# board_power_supply_lm26480.net
KiCad netlist of a schematic drawn in EAGLE
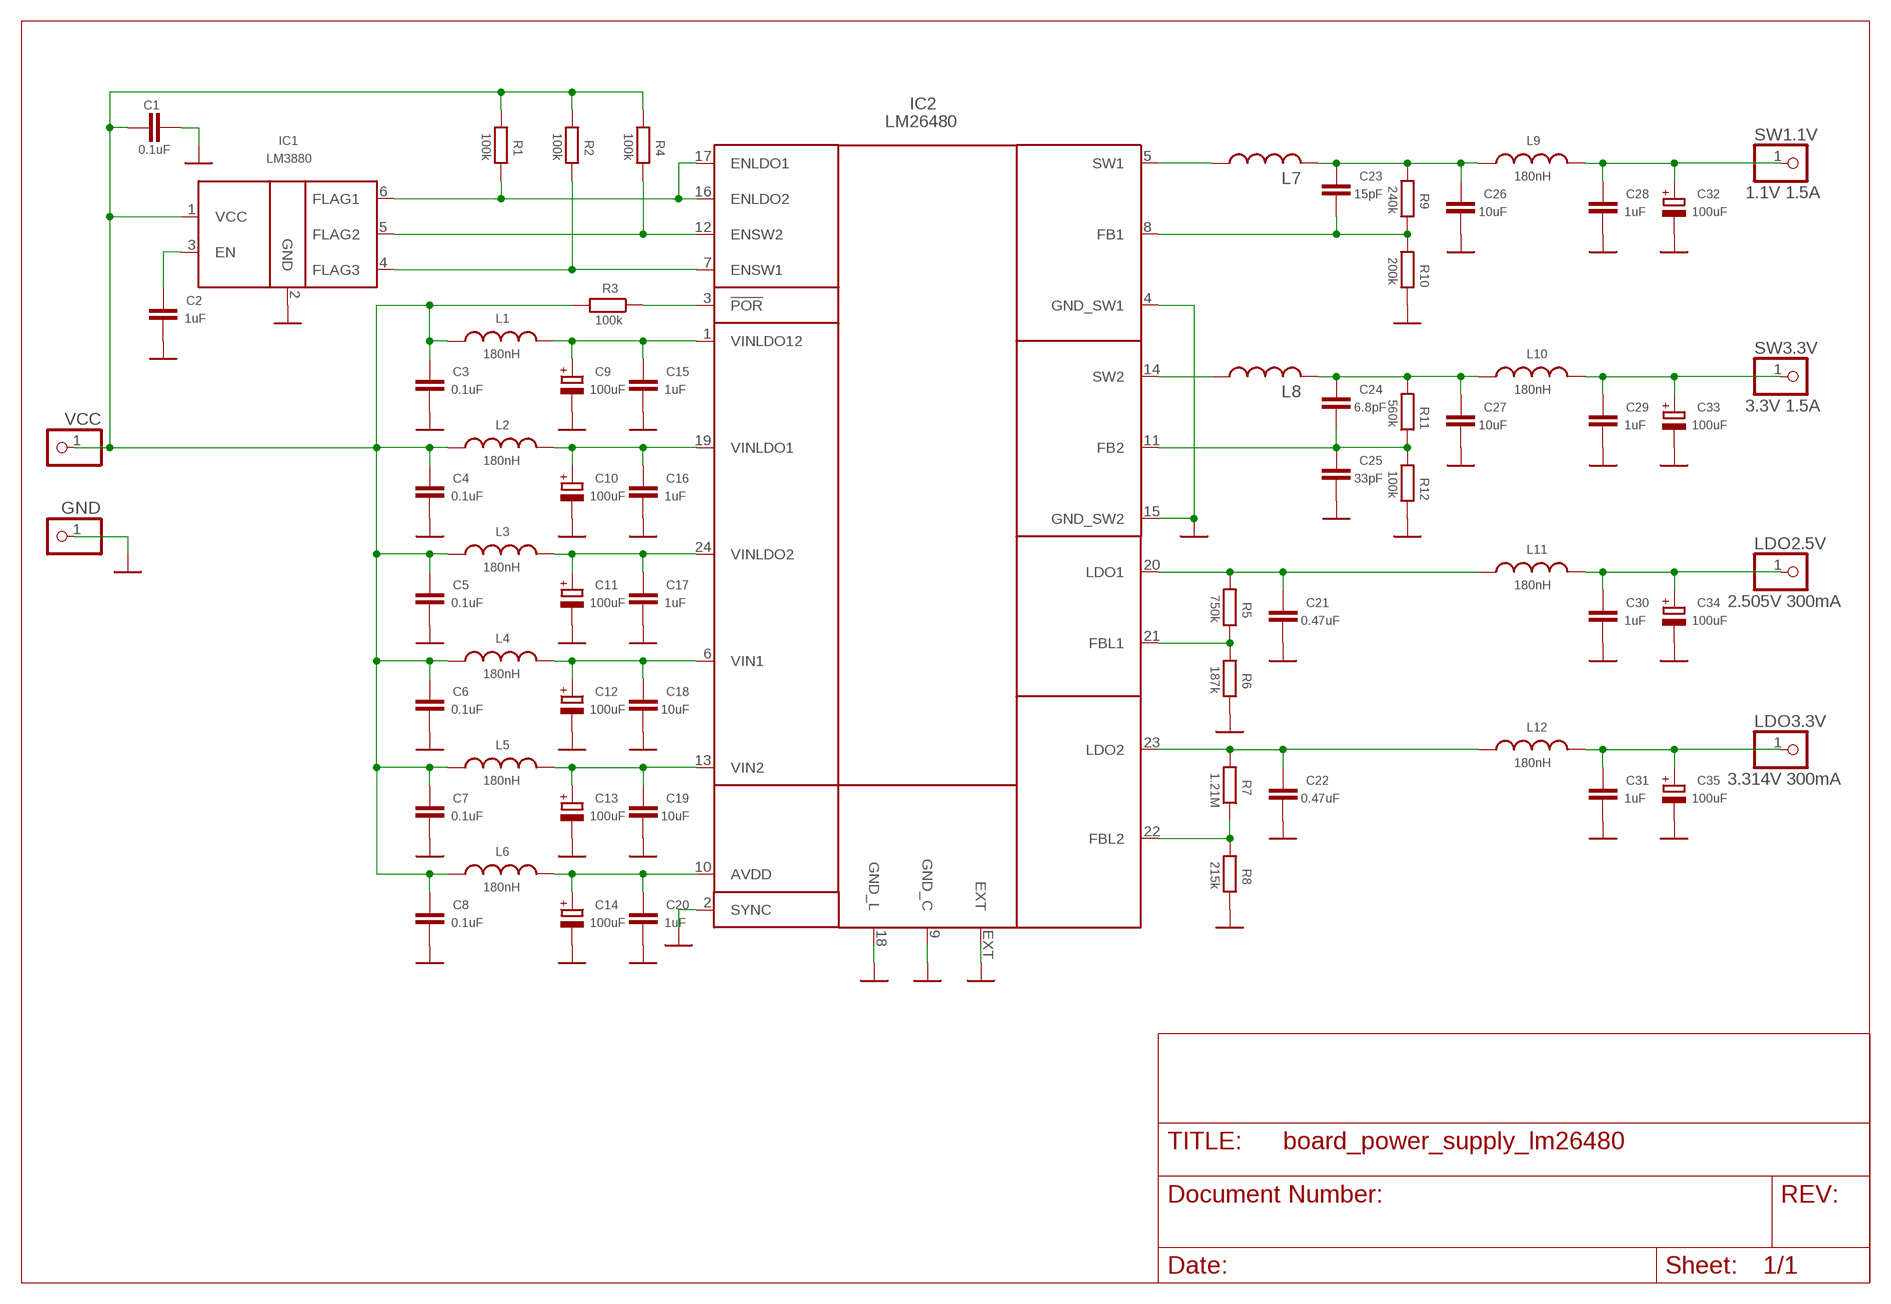
[diagram p0: schematic, sheet 1]

(export (version "E")
  (design (tool "Eeschema 10.0.6"))
  (components
    (comp (ref "C1")
      (value "0.1uF")
      (footprint "eagle-import:SMD0603")
      (libsource (lib "eagle-import") (part "C0603"))
    )
    (comp (ref "C2")
      (value "1uF")
      (footprint "eagle-import:SMD0603")
      (libsource (lib "eagle-import") (part "C0603"))
    )
    (comp (ref "C3")
      (value "0.1uF")
      (footprint "eagle-import:SMD0603")
      (libsource (lib "eagle-import") (part "C0603"))
    )
    (comp (ref "C4")
      (value "0.1uF")
      (footprint "eagle-import:SMD0603")
      (libsource (lib "eagle-import") (part "C0603"))
    )
    (comp (ref "C5")
      (value "0.1uF")
      (footprint "eagle-import:SMD0603")
      (libsource (lib "eagle-import") (part "C0603"))
    )
    (comp (ref "C6")
      (value "0.1uF")
      (footprint "eagle-import:SMD0603")
      (libsource (lib "eagle-import") (part "C0603"))
    )
    (comp (ref "C7")
      (value "0.1uF")
      (footprint "eagle-import:SMD0603")
      (libsource (lib "eagle-import") (part "C0603"))
    )
    (comp (ref "C8")
      (value "0.1uF")
      (footprint "eagle-import:SMD0603")
      (libsource (lib "eagle-import") (part "C0603"))
    )
    (comp (ref "C9")
      (value "100uF")
      (footprint "eagle-import:SMC_B")
      (libsource (lib "eagle-import") (part "CPOLSMC_B"))
    )
    (comp (ref "C10")
      (value "100uF")
      (footprint "eagle-import:SMC_B")
      (libsource (lib "eagle-import") (part "CPOLSMC_B"))
    )
    (comp (ref "C11")
      (value "100uF")
      (footprint "eagle-import:SMC_B")
      (libsource (lib "eagle-import") (part "CPOLSMC_B"))
    )
    (comp (ref "C12")
      (value "100uF")
      (footprint "eagle-import:SMC_B")
      (libsource (lib "eagle-import") (part "CPOLSMC_B"))
    )
    (comp (ref "C13")
      (value "100uF")
      (footprint "eagle-import:SMC_B")
      (libsource (lib "eagle-import") (part "CPOLSMC_B"))
    )
    (comp (ref "C14")
      (value "100uF")
      (footprint "eagle-import:SMC_B")
      (libsource (lib "eagle-import") (part "CPOLSMC_B"))
    )
    (comp (ref "C15")
      (value "1uF")
      (footprint "eagle-import:SMD0402")
      (libsource (lib "eagle-import") (part "C0402"))
    )
    (comp (ref "C16")
      (value "1uF")
      (footprint "eagle-import:SMD0402")
      (libsource (lib "eagle-import") (part "C0402"))
    )
    (comp (ref "C17")
      (value "1uF")
      (footprint "eagle-import:SMD0402")
      (libsource (lib "eagle-import") (part "C0402"))
    )
    (comp (ref "C18")
      (value "10uF")
      (footprint "eagle-import:SMD0805")
      (libsource (lib "eagle-import") (part "C0805"))
    )
    (comp (ref "C19")
      (value "10uF")
      (footprint "eagle-import:SMD0805")
      (libsource (lib "eagle-import") (part "C0805"))
    )
    (comp (ref "C20")
      (value "1uF")
      (footprint "eagle-import:SMD0402")
      (libsource (lib "eagle-import") (part "C0402"))
    )
    (comp (ref "C21")
      (value "0.47uF")
      (footprint "eagle-import:SMD0603")
      (libsource (lib "eagle-import") (part "C0603"))
    )
    (comp (ref "C22")
      (value "0.47uF")
      (footprint "eagle-import:SMD0603")
      (libsource (lib "eagle-import") (part "C0603"))
    )
    (comp (ref "C23")
      (value "15pF")
      (footprint "eagle-import:SMD0603")
      (libsource (lib "eagle-import") (part "C0603"))
    )
    (comp (ref "C24")
      (value "6.8pF")
      (footprint "eagle-import:SMD0603")
      (libsource (lib "eagle-import") (part "C0603"))
    )
    (comp (ref "C25")
      (value "33pF")
      (footprint "eagle-import:SMD0603")
      (libsource (lib "eagle-import") (part "C0603"))
    )
    (comp (ref "C26")
      (value "10uF")
      (footprint "eagle-import:SMD0805")
      (libsource (lib "eagle-import") (part "C0805"))
    )
    (comp (ref "C27")
      (value "10uF")
      (footprint "eagle-import:SMD0805")
      (libsource (lib "eagle-import") (part "C0805"))
    )
    (comp (ref "C28")
      (value "1uF")
      (footprint "eagle-import:SMD0603")
      (libsource (lib "eagle-import") (part "C0603"))
    )
    (comp (ref "C29")
      (value "1uF")
      (footprint "eagle-import:SMD0603")
      (libsource (lib "eagle-import") (part "C0603"))
    )
    (comp (ref "C30")
      (value "1uF")
      (footprint "eagle-import:SMD0603")
      (libsource (lib "eagle-import") (part "C0603"))
    )
    (comp (ref "C31")
      (value "1uF")
      (footprint "eagle-import:SMD0603")
      (libsource (lib "eagle-import") (part "C0603"))
    )
    (comp (ref "C32")
      (value "100uF")
      (footprint "eagle-import:SMC_B")
      (libsource (lib "eagle-import") (part "CPOLSMC_B"))
    )
    (comp (ref "C33")
      (value "100uF")
      (footprint "eagle-import:SMC_B")
      (libsource (lib "eagle-import") (part "CPOLSMC_B"))
    )
    (comp (ref "C34")
      (value "100uF")
      (footprint "eagle-import:SMC_B")
      (libsource (lib "eagle-import") (part "CPOLSMC_B"))
    )
    (comp (ref "C35")
      (value "100uF")
      (footprint "eagle-import:SMC_B")
      (libsource (lib "eagle-import") (part "CPOLSMC_B"))
    )
    (comp (ref "GND")
      (value "PINHD-1X1")
      (footprint "eagle-import:1X01")
      (libsource (lib "eagle-import") (part "PINHD-1X1"))
    )
    (comp (ref "IC1")
      (value "LM3880")
      (footprint "eagle-import:SOT23-6")
      (libsource (lib "eagle-import") (part "LM3880"))
    )
    (comp (ref "IC2")
      (value "LM26480")
      (footprint "eagle-import:WQFN24")
      (libsource (lib "eagle-import") (part "LM26480SQ-AA/NOPB"))
    )
    (comp (ref "L1")
      (value "180nH")
      (footprint "eagle-import:SMD0603")
      (libsource (lib "eagle-import") (part "L0603"))
    )
    (comp (ref "L2")
      (value "180nH")
      (footprint "eagle-import:SMD0603")
      (libsource (lib "eagle-import") (part "L0603"))
    )
    (comp (ref "L3")
      (value "180nH")
      (footprint "eagle-import:SMD0603")
      (libsource (lib "eagle-import") (part "L0603"))
    )
    (comp (ref "L4")
      (value "180nH")
      (footprint "eagle-import:SMD0603")
      (libsource (lib "eagle-import") (part "L0603"))
    )
    (comp (ref "L5")
      (value "180nH")
      (footprint "eagle-import:SMD0603")
      (libsource (lib "eagle-import") (part "L0603"))
    )
    (comp (ref "L6")
      (value "180nH")
      (footprint "eagle-import:SMD0603")
      (libsource (lib "eagle-import") (part "L0603"))
    )
    (comp (ref "L7")
      (value "L2825")
      (footprint "eagle-import:L2825P")
      (libsource (lib "eagle-import") (part "L2825"))
    )
    (comp (ref "L8")
      (value "L2825")
      (footprint "eagle-import:L2825P")
      (libsource (lib "eagle-import") (part "L2825"))
    )
    (comp (ref "L9")
      (value "180nH")
      (footprint "eagle-import:SMD0603")
      (libsource (lib "eagle-import") (part "L0603"))
    )
    (comp (ref "L10")
      (value "180nH")
      (footprint "eagle-import:SMD0603")
      (libsource (lib "eagle-import") (part "L0603"))
    )
    (comp (ref "L11")
      (value "180nH")
      (footprint "eagle-import:SMD0603")
      (libsource (lib "eagle-import") (part "L0603"))
    )
    (comp (ref "L12")
      (value "180nH")
      (footprint "eagle-import:SMD0603")
      (libsource (lib "eagle-import") (part "L0603"))
    )
    (comp (ref "LDO2.5V")
      (value "PINHD-1X1")
      (footprint "eagle-import:1X01")
      (libsource (lib "eagle-import") (part "PINHD-1X1"))
    )
    (comp (ref "LDO3.3V")
      (value "PINHD-1X1")
      (footprint "eagle-import:1X01")
      (libsource (lib "eagle-import") (part "PINHD-1X1"))
    )
    (comp (ref "R1")
      (value "100k")
      (footprint "eagle-import:SMD0603")
      (libsource (lib "eagle-import") (part "R0603"))
    )
    (comp (ref "R2")
      (value "100k")
      (footprint "eagle-import:SMD0603")
      (libsource (lib "eagle-import") (part "R0603"))
    )
    (comp (ref "R3")
      (value "100k")
      (footprint "eagle-import:SMD0402")
      (libsource (lib "eagle-import") (part "R0402"))
    )
    (comp (ref "R4")
      (value "100k")
      (footprint "eagle-import:SMD0603")
      (libsource (lib "eagle-import") (part "R0603"))
    )
    (comp (ref "R5")
      (value "750k")
      (footprint "eagle-import:SMD0603")
      (libsource (lib "eagle-import") (part "R0603"))
    )
    (comp (ref "R6")
      (value "187k")
      (footprint "eagle-import:SMD0603")
      (libsource (lib "eagle-import") (part "R0603"))
    )
    (comp (ref "R7")
      (value "1.21M")
      (footprint "eagle-import:SMD0603")
      (libsource (lib "eagle-import") (part "R0603"))
    )
    (comp (ref "R8")
      (value "215k")
      (footprint "eagle-import:SMD0603")
      (libsource (lib "eagle-import") (part "R0603"))
    )
    (comp (ref "R9")
      (value "240k")
      (footprint "eagle-import:SMD0603")
      (libsource (lib "eagle-import") (part "R0603"))
    )
    (comp (ref "R10")
      (value "200k")
      (footprint "eagle-import:SMD0603")
      (libsource (lib "eagle-import") (part "R0603"))
    )
    (comp (ref "R11")
      (value "560k")
      (footprint "eagle-import:SMD0603")
      (libsource (lib "eagle-import") (part "R0603"))
    )
    (comp (ref "R12")
      (value "100k")
      (footprint "eagle-import:SMD0603")
      (libsource (lib "eagle-import") (part "R0603"))
    )
    (comp (ref "SW1.1V")
      (value "PINHD-1X1")
      (footprint "eagle-import:1X01")
      (libsource (lib "eagle-import") (part "PINHD-1X1"))
    )
    (comp (ref "SW3.3V")
      (value "PINHD-1X1")
      (footprint "eagle-import:1X01")
      (libsource (lib "eagle-import") (part "PINHD-1X1"))
    )
    (comp (ref "VCC")
      (value "PINHD-1X1")
      (footprint "eagle-import:1X01")
      (libsource (lib "eagle-import") (part "PINHD-1X1"))
    )
  )
  (nets
    (net (code "1") (name "GND") (class "Default")
      (node (ref "C1") (pin "1") (pinfunction "1_1") (pintype "passive"))
      (node (ref "C10") (pin "-") (pinfunction "-_-") (pintype "passive"))
      (node (ref "C11") (pin "-") (pinfunction "-_-") (pintype "passive"))
      (node (ref "C12") (pin "-") (pinfunction "-_-") (pintype "passive"))
      (node (ref "C13") (pin "-") (pinfunction "-_-") (pintype "passive"))
      (node (ref "C14") (pin "-") (pinfunction "-_-") (pintype "passive"))
      (node (ref "C15") (pin "2") (pinfunction "2_2") (pintype "passive"))
      (node (ref "C16") (pin "2") (pinfunction "2_2") (pintype "passive"))
      (node (ref "C17") (pin "2") (pinfunction "2_2") (pintype "passive"))
      (node (ref "C18") (pin "2") (pinfunction "2_2") (pintype "passive"))
      (node (ref "C19") (pin "2") (pinfunction "2_2") (pintype "passive"))
      (node (ref "C2") (pin "2") (pinfunction "2_2") (pintype "passive"))
      (node (ref "C20") (pin "2") (pinfunction "2_2") (pintype "passive"))
      (node (ref "C21") (pin "2") (pinfunction "2_2") (pintype "passive"))
      (node (ref "C22") (pin "2") (pinfunction "2_2") (pintype "passive"))
      (node (ref "C25") (pin "2") (pinfunction "2_2") (pintype "passive"))
      (node (ref "C26") (pin "2") (pinfunction "2_2") (pintype "passive"))
      (node (ref "C27") (pin "2") (pinfunction "2_2") (pintype "passive"))
      (node (ref "C28") (pin "2") (pinfunction "2_2") (pintype "passive"))
      (node (ref "C29") (pin "2") (pinfunction "2_2") (pintype "passive"))
      (node (ref "C3") (pin "2") (pinfunction "2_2") (pintype "passive"))
      (node (ref "C30") (pin "2") (pinfunction "2_2") (pintype "passive"))
      (node (ref "C31") (pin "2") (pinfunction "2_2") (pintype "passive"))
      (node (ref "C32") (pin "-") (pinfunction "-_-") (pintype "passive"))
      (node (ref "C33") (pin "-") (pinfunction "-_-") (pintype "passive"))
      (node (ref "C34") (pin "-") (pinfunction "-_-") (pintype "passive"))
      (node (ref "C35") (pin "-") (pinfunction "-_-") (pintype "passive"))
      (node (ref "C4") (pin "2") (pinfunction "2_2") (pintype "passive"))
      (node (ref "C5") (pin "2") (pinfunction "2_2") (pintype "passive"))
      (node (ref "C6") (pin "2") (pinfunction "2_2") (pintype "passive"))
      (node (ref "C7") (pin "2") (pinfunction "2_2") (pintype "passive"))
      (node (ref "C8") (pin "2") (pinfunction "2_2") (pintype "passive"))
      (node (ref "C9") (pin "-") (pinfunction "-_-") (pintype "passive"))
      (node (ref "GND") (pin "1") (pinfunction "1_1") (pintype "passive"))
      (node (ref "IC1") (pin "2") (pinfunction "GND_2") (pintype "power_in"))
      (node (ref "IC2") (pin "15") (pinfunction "GND_SW2_15") (pintype "power_in"))
      (node (ref "IC2") (pin "18") (pinfunction "GND_L_18") (pintype "power_in"))
      (node (ref "IC2") (pin "2") (pinfunction "SYNC_2") (pintype "input"))
      (node (ref "IC2") (pin "4") (pinfunction "GND_SW1_4") (pintype "power_in"))
      (node (ref "IC2") (pin "9") (pinfunction "GND_C_9") (pintype "power_in"))
      (node (ref "IC2") (pin "EXT") (pinfunction "EXT_EXT") (pintype "power_in"))
      (node (ref "R10") (pin "1") (pinfunction "1_1") (pintype "passive"))
      (node (ref "R12") (pin "1") (pinfunction "1_1") (pintype "passive"))
      (node (ref "R6") (pin "1") (pinfunction "1_1") (pintype "passive"))
      (node (ref "R8") (pin "1") (pinfunction "1_1") (pintype "passive"))
    )
    (net (code "2") (name "Net-(C23-Pad1)") (class "Default")
      (node (ref "C23") (pin "1") (pinfunction "1_1") (pintype "passive"))
      (node (ref "C26") (pin "1") (pinfunction "1_1") (pintype "passive"))
      (node (ref "L7") (pin "2") (pinfunction "2_2") (pintype "passive"))
      (node (ref "L9") (pin "1") (pinfunction "1_1") (pintype "passive"))
      (node (ref "R9") (pin "2") (pinfunction "2_2") (pintype "passive"))
    )
    (net (code "3") (name "Net-(C24-Pad1)") (class "Default")
      (node (ref "C24") (pin "1") (pinfunction "1_1") (pintype "passive"))
      (node (ref "C27") (pin "1") (pinfunction "1_1") (pintype "passive"))
      (node (ref "L10") (pin "1") (pinfunction "1_1") (pintype "passive"))
      (node (ref "L8") (pin "2") (pinfunction "2_2") (pintype "passive"))
      (node (ref "R11") (pin "2") (pinfunction "2_2") (pintype "passive"))
    )
    (net (code "4") (name "Net-(C28-Pad1)") (class "Default")
      (node (ref "C28") (pin "1") (pinfunction "1_1") (pintype "passive"))
      (node (ref "C32") (pin "+") (pinfunction "+_+") (pintype "passive"))
      (node (ref "L9") (pin "2") (pinfunction "2_2") (pintype "passive"))
      (node (ref "SW1.1V") (pin "1") (pinfunction "1_1") (pintype "passive"))
    )
    (net (code "5") (name "Net-(C29-Pad1)") (class "Default")
      (node (ref "C29") (pin "1") (pinfunction "1_1") (pintype "passive"))
      (node (ref "C33") (pin "+") (pinfunction "+_+") (pintype "passive"))
      (node (ref "L10") (pin "2") (pinfunction "2_2") (pintype "passive"))
      (node (ref "SW3.3V") (pin "1") (pinfunction "1_1") (pintype "passive"))
    )
    (net (code "6") (name "Net-(C30-Pad1)") (class "Default")
      (node (ref "C30") (pin "1") (pinfunction "1_1") (pintype "passive"))
      (node (ref "C34") (pin "+") (pinfunction "+_+") (pintype "passive"))
      (node (ref "L11") (pin "2") (pinfunction "2_2") (pintype "passive"))
      (node (ref "LDO2.5V") (pin "1") (pinfunction "1_1") (pintype "passive"))
    )
    (net (code "7") (name "Net-(C31-Pad1)") (class "Default")
      (node (ref "C31") (pin "1") (pinfunction "1_1") (pintype "passive"))
      (node (ref "C35") (pin "+") (pinfunction "+_+") (pintype "passive"))
      (node (ref "L12") (pin "2") (pinfunction "2_2") (pintype "passive"))
      (node (ref "LDO3.3V") (pin "1") (pinfunction "1_1") (pintype "passive"))
    )
    (net (code "8") (name "Net-(IC1-EN)") (class "Default")
      (node (ref "C2") (pin "1") (pinfunction "1_1") (pintype "passive"))
      (node (ref "IC1") (pin "3") (pinfunction "EN_3") (pintype "input"))
    )
    (net (code "9") (name "Net-(IC1-FLAG1)") (class "Default")
      (node (ref "IC1") (pin "6") (pinfunction "FLAG1_6") (pintype "output"))
      (node (ref "IC2") (pin "16") (pinfunction "ENLDO2_16") (pintype "input"))
      (node (ref "IC2") (pin "17") (pinfunction "ENLDO1_17") (pintype "input"))
      (node (ref "R1") (pin "1") (pinfunction "1_1") (pintype "passive"))
    )
    (net (code "10") (name "Net-(IC1-FLAG2)") (class "Default")
      (node (ref "IC1") (pin "5") (pinfunction "FLAG2_5") (pintype "output"))
      (node (ref "IC2") (pin "12") (pinfunction "ENSW2_12") (pintype "power_in"))
      (node (ref "R4") (pin "1") (pinfunction "1_1") (pintype "passive"))
    )
    (net (code "11") (name "Net-(IC1-FLAG3)") (class "Default")
      (node (ref "IC1") (pin "4") (pinfunction "FLAG3_4") (pintype "output"))
      (node (ref "IC2") (pin "7") (pinfunction "ENSW1_7") (pintype "power_in"))
      (node (ref "R2") (pin "1") (pinfunction "1_1") (pintype "passive"))
    )
    (net (code "12") (name "Net-(IC1-VCC)") (class "Default")
      (node (ref "C1") (pin "2") (pinfunction "2_2") (pintype "passive"))
      (node (ref "C3") (pin "1") (pinfunction "1_1") (pintype "passive"))
      (node (ref "C4") (pin "1") (pinfunction "1_1") (pintype "passive"))
      (node (ref "C5") (pin "1") (pinfunction "1_1") (pintype "passive"))
      (node (ref "C6") (pin "1") (pinfunction "1_1") (pintype "passive"))
      (node (ref "C7") (pin "1") (pinfunction "1_1") (pintype "passive"))
      (node (ref "C8") (pin "1") (pinfunction "1_1") (pintype "passive"))
      (node (ref "IC1") (pin "1") (pinfunction "VCC_1") (pintype "power_in"))
      (node (ref "L1") (pin "1") (pinfunction "1_1") (pintype "passive"))
      (node (ref "L2") (pin "1") (pinfunction "1_1") (pintype "passive"))
      (node (ref "L3") (pin "1") (pinfunction "1_1") (pintype "passive"))
      (node (ref "L4") (pin "1") (pinfunction "1_1") (pintype "passive"))
      (node (ref "L5") (pin "1") (pinfunction "1_1") (pintype "passive"))
      (node (ref "L6") (pin "1") (pinfunction "1_1") (pintype "passive"))
      (node (ref "R1") (pin "2") (pinfunction "2_2") (pintype "passive"))
      (node (ref "R2") (pin "2") (pinfunction "2_2") (pintype "passive"))
      (node (ref "R3") (pin "2") (pinfunction "2_2") (pintype "passive"))
      (node (ref "R4") (pin "2") (pinfunction "2_2") (pintype "passive"))
      (node (ref "VCC") (pin "1") (pinfunction "1_1") (pintype "passive"))
    )
    (net (code "13") (name "Net-(IC2-AVDD)") (class "Default")
      (node (ref "C14") (pin "+") (pinfunction "+_+") (pintype "passive"))
      (node (ref "C20") (pin "1") (pinfunction "1_1") (pintype "passive"))
      (node (ref "IC2") (pin "10") (pinfunction "AVDD_10") (pintype "power_in"))
      (node (ref "L6") (pin "2") (pinfunction "2_2") (pintype "passive"))
    )
    (net (code "14") (name "Net-(IC2-FB1)") (class "Default")
      (node (ref "C23") (pin "2") (pinfunction "2_2") (pintype "passive"))
      (node (ref "IC2") (pin "8") (pinfunction "FB1_8") (pintype "power_in"))
      (node (ref "R10") (pin "2") (pinfunction "2_2") (pintype "passive"))
      (node (ref "R9") (pin "1") (pinfunction "1_1") (pintype "passive"))
    )
    (net (code "15") (name "Net-(IC2-FB2)") (class "Default")
      (node (ref "C24") (pin "2") (pinfunction "2_2") (pintype "passive"))
      (node (ref "C25") (pin "1") (pinfunction "1_1") (pintype "passive"))
      (node (ref "IC2") (pin "11") (pinfunction "FB2_11") (pintype "power_in"))
      (node (ref "R11") (pin "1") (pinfunction "1_1") (pintype "passive"))
      (node (ref "R12") (pin "2") (pinfunction "2_2") (pintype "passive"))
    )
    (net (code "16") (name "Net-(IC2-FBL1)") (class "Default")
      (node (ref "IC2") (pin "21") (pinfunction "FBL1_21") (pintype "input"))
      (node (ref "R5") (pin "1") (pinfunction "1_1") (pintype "passive"))
      (node (ref "R6") (pin "2") (pinfunction "2_2") (pintype "passive"))
    )
    (net (code "17") (name "Net-(IC2-FBL2)") (class "Default")
      (node (ref "IC2") (pin "22") (pinfunction "FBL2_22") (pintype "input"))
      (node (ref "R7") (pin "1") (pinfunction "1_1") (pintype "passive"))
      (node (ref "R8") (pin "2") (pinfunction "2_2") (pintype "passive"))
    )
    (net (code "18") (name "Net-(IC2-LDO1)") (class "Default")
      (node (ref "C21") (pin "1") (pinfunction "1_1") (pintype "passive"))
      (node (ref "IC2") (pin "20") (pinfunction "LDO1_20") (pintype "power_in"))
      (node (ref "L11") (pin "1") (pinfunction "1_1") (pintype "passive"))
      (node (ref "R5") (pin "2") (pinfunction "2_2") (pintype "passive"))
    )
    (net (code "19") (name "Net-(IC2-LDO2)") (class "Default")
      (node (ref "C22") (pin "1") (pinfunction "1_1") (pintype "passive"))
      (node (ref "IC2") (pin "23") (pinfunction "LDO2_23") (pintype "power_in"))
      (node (ref "L12") (pin "1") (pinfunction "1_1") (pintype "passive"))
      (node (ref "R7") (pin "2") (pinfunction "2_2") (pintype "passive"))
    )
    (net (code "20") (name "Net-(IC2-SW1)") (class "Default")
      (node (ref "IC2") (pin "5") (pinfunction "SW1_5") (pintype "power_in"))
      (node (ref "L7") (pin "1") (pinfunction "1_1") (pintype "passive"))
    )
    (net (code "21") (name "Net-(IC2-SW2)") (class "Default")
      (node (ref "IC2") (pin "14") (pinfunction "SW2_14") (pintype "power_in"))
      (node (ref "L8") (pin "1") (pinfunction "1_1") (pintype "passive"))
    )
    (net (code "22") (name "Net-(IC2-VIN1)") (class "Default")
      (node (ref "C12") (pin "+") (pinfunction "+_+") (pintype "passive"))
      (node (ref "C18") (pin "1") (pinfunction "1_1") (pintype "passive"))
      (node (ref "IC2") (pin "6") (pinfunction "VIN1_6") (pintype "power_in"))
      (node (ref "L4") (pin "2") (pinfunction "2_2") (pintype "passive"))
    )
    (net (code "23") (name "Net-(IC2-VIN2)") (class "Default")
      (node (ref "C13") (pin "+") (pinfunction "+_+") (pintype "passive"))
      (node (ref "C19") (pin "1") (pinfunction "1_1") (pintype "passive"))
      (node (ref "IC2") (pin "13") (pinfunction "VIN2_13") (pintype "power_in"))
      (node (ref "L5") (pin "2") (pinfunction "2_2") (pintype "passive"))
    )
    (net (code "24") (name "Net-(IC2-VINLDO1)") (class "Default")
      (node (ref "C10") (pin "+") (pinfunction "+_+") (pintype "passive"))
      (node (ref "C16") (pin "1") (pinfunction "1_1") (pintype "passive"))
      (node (ref "IC2") (pin "19") (pinfunction "VINLDO1_19") (pintype "power_in"))
      (node (ref "L2") (pin "2") (pinfunction "2_2") (pintype "passive"))
    )
    (net (code "25") (name "Net-(IC2-VINLDO2)") (class "Default")
      (node (ref "C11") (pin "+") (pinfunction "+_+") (pintype "passive"))
      (node (ref "C17") (pin "1") (pinfunction "1_1") (pintype "passive"))
      (node (ref "IC2") (pin "24") (pinfunction "VINLDO2_24") (pintype "power_in"))
      (node (ref "L3") (pin "2") (pinfunction "2_2") (pintype "passive"))
    )
    (net (code "26") (name "Net-(IC2-VINLDO12)") (class "Default")
      (node (ref "C15") (pin "1") (pinfunction "1_1") (pintype "passive"))
      (node (ref "C9") (pin "+") (pinfunction "+_+") (pintype "passive"))
      (node (ref "IC2") (pin "1") (pinfunction "VINLDO12_1") (pintype "power_in"))
      (node (ref "L1") (pin "2") (pinfunction "2_2") (pintype "passive"))
    )
    (net (code "27") (name "Net-(IC2-~{POR})") (class "Default")
      (node (ref "IC2") (pin "3") (pinfunction "~{POR}_3") (pintype "output"))
      (node (ref "R3") (pin "1") (pinfunction "1_1") (pintype "passive"))
    )
  )
)
